# Schematic.net
KiCad netlist of a schematic drawn in EAGLE
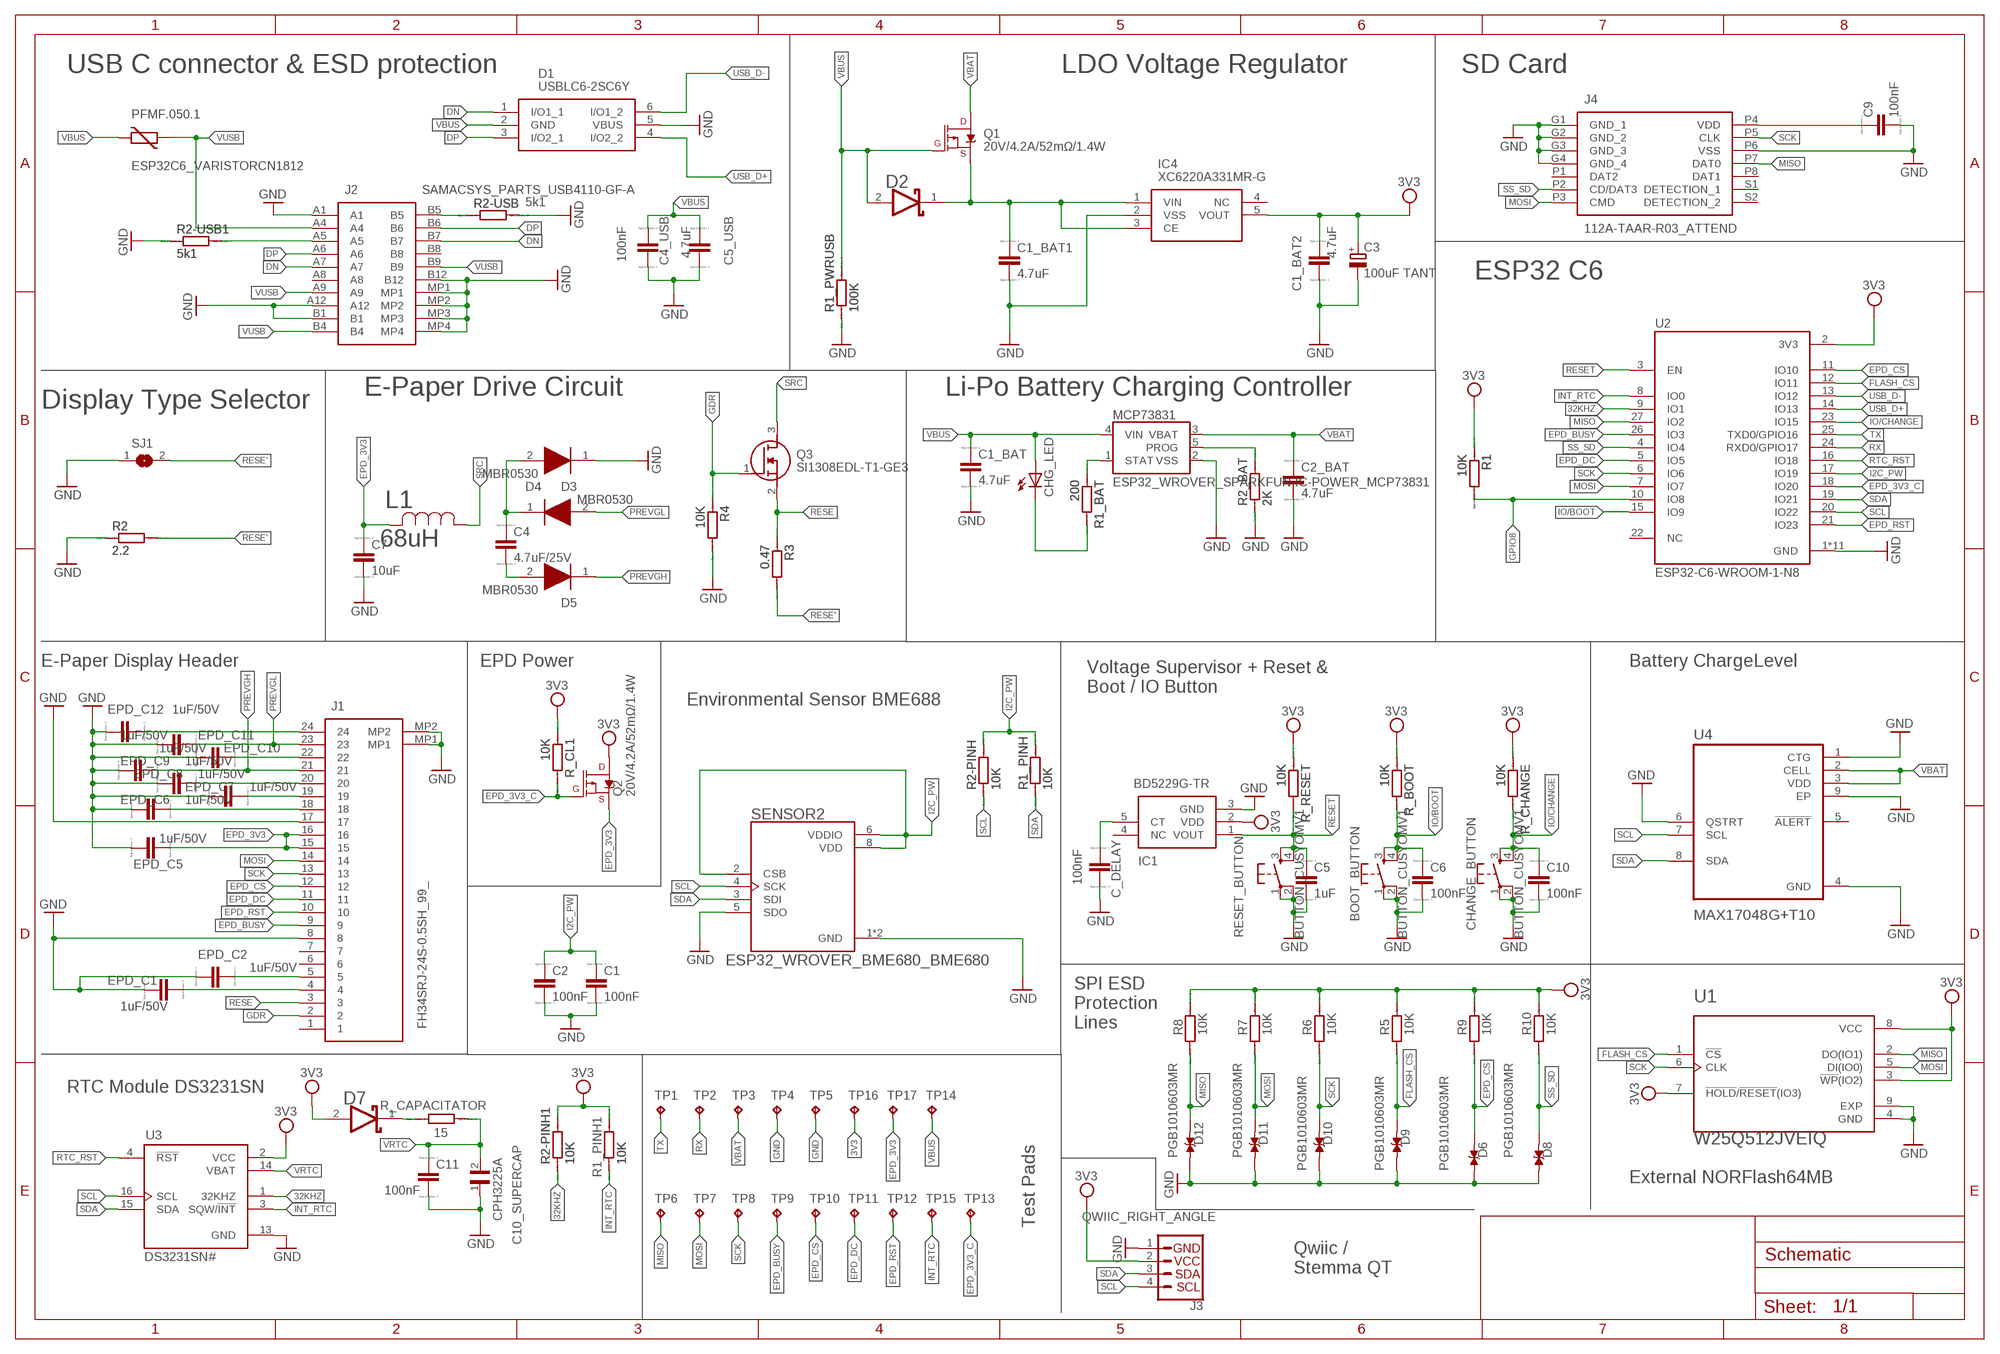
[diagram p0: schematic, sheet 1]

(export (version "E")
  (design (tool "Eeschema 10.0.6"))
  (components
    (comp (ref "BOOT_BUTTON")
      (value "BUTTON_CUSYOMV1")
      (footprint "eagle-import:MYBUTTON")
      (libsource (lib "eagle-import") (part "BUTTON_CUSYOMV1"))
    )
    (comp (ref "C1")
      (value "100nF")
      (footprint "eagle-import:EAGLE-LTSPICE_C0402")
      (libsource (lib "eagle-import") (part "EAGLE-LTSPICE_CC0402"))
    )
    (comp (ref "C1_BAT")
      (value "4.7uF")
      (footprint "eagle-import:EAGLE-LTSPICE_C0402")
      (libsource (lib "eagle-import") (part "EAGLE-LTSPICE_CC0402"))
    )
    (comp (ref "C1_BAT1")
      (value "4.7uF")
      (footprint "eagle-import:EAGLE-LTSPICE_C0402")
      (libsource (lib "eagle-import") (part "EAGLE-LTSPICE_CC0402"))
    )
    (comp (ref "C1_BAT2")
      (value "4.7uF")
      (footprint "eagle-import:ESP32_WROVER_EAGLE-LTSPICE_C0402")
      (libsource (lib "eagle-import") (part "ESP32_WROVER_EAGLE-LTSPICE_CC0402"))
    )
    (comp (ref "C2")
      (value "100nF")
      (footprint "eagle-import:EAGLE-LTSPICE_C0402")
      (libsource (lib "eagle-import") (part "EAGLE-LTSPICE_CC0402"))
    )
    (comp (ref "C2_BAT")
      (value "4.7uF")
      (footprint "eagle-import:ESP32_WROVER_EAGLE-LTSPICE_C0402")
      (libsource (lib "eagle-import") (part "ESP32_WROVER_EAGLE-LTSPICE_CC0402"))
    )
    (comp (ref "C3")
      (value "100uF TANT")
      (footprint "eagle-import:RCL_CT3528")
      (libsource (lib "eagle-import") (part "RCL_CPOL-EUCT3528"))
    )
    (comp (ref "C4")
      (value "4.7uF/25V")
      (footprint "eagle-import:ESP32_WROVER_EAGLE-LTSPICE_C0402")
      (libsource (lib "eagle-import") (part "ESP32_WROVER_EAGLE-LTSPICE_CC0402"))
    )
    (comp (ref "C4_USB")
      (value "100nF")
      (footprint "eagle-import:EAGLE-LTSPICE_C0402")
      (libsource (lib "eagle-import") (part "EAGLE-LTSPICE_CC0402"))
    )
    (comp (ref "C5")
      (value "1uF")
      (footprint "eagle-import:EAGLE-LTSPICE_C0402")
      (libsource (lib "eagle-import") (part "EAGLE-LTSPICE_CC0402"))
    )
    (comp (ref "C5_USB")
      (value "4.7uF")
      (footprint "eagle-import:EAGLE-LTSPICE_C0402")
      (libsource (lib "eagle-import") (part "EAGLE-LTSPICE_CC0402"))
    )
    (comp (ref "C6")
      (value "100nF")
      (footprint "eagle-import:EAGLE-LTSPICE_C0402")
      (libsource (lib "eagle-import") (part "EAGLE-LTSPICE_CC0402"))
    )
    (comp (ref "C7")
      (value "10uF")
      (footprint "eagle-import:EAGLE-LTSPICE_C0402")
      (libsource (lib "eagle-import") (part "EAGLE-LTSPICE_CC0402"))
    )
    (comp (ref "C9")
      (value "100nF")
      (footprint "eagle-import:ESP32_WROVER_EAGLE-LTSPICE_C0402")
      (libsource (lib "eagle-import") (part "ESP32_WROVER_EAGLE-LTSPICE_CC0402"))
    )
    (comp (ref "C10")
      (value "100nF")
      (footprint "eagle-import:EAGLE-LTSPICE_C0402")
      (libsource (lib "eagle-import") (part "EAGLE-LTSPICE_CC0402"))
    )
    (comp (ref "C10_SUPERCAP")
      (value "CPH3225A")
      (footprint "eagle-import:CAPCP3225X100N")
      (fields (field (name "MF") "Seiko Instruments"))
      (libsource (lib "eagle-import") (part "CPH3225A"))
    )
    (comp (ref "C11")
      (value "100nF")
      (footprint "eagle-import:ESP32_WROVER_EAGLE-LTSPICE_C0402")
      (libsource (lib "eagle-import") (part "ESP32_WROVER_EAGLE-LTSPICE_CC0402"))
    )
    (comp (ref "CHANGE_BUTTON")
      (value "BUTTON_CUSYOMV1")
      (footprint "eagle-import:MYBUTTON")
      (libsource (lib "eagle-import") (part "BUTTON_CUSYOMV1"))
    )
    (comp (ref "CHG_LED")
      (value "ADAFRUIT_LEDCHIP-LED0603")
      (footprint "eagle-import:ADAFRUIT_CHIP-LED0603")
      (libsource (lib "eagle-import") (part "ADAFRUIT_LEDCHIP-LED0603"))
    )
    (comp (ref "C_DELAY")
      (value "100nF")
      (footprint "eagle-import:EAGLE-LTSPICE_C0402")
      (libsource (lib "eagle-import") (part "EAGLE-LTSPICE_CC0402"))
    )
    (comp (ref "D1")
      (value "USBLC6-2SC6Y")
      (footprint "eagle-import:SOT95P280X145-6N")
      (fields (field (name "MF") "STMicroelectronics"))
      (libsource (lib "eagle-import") (part "USBLC6-2SC6Y"))
    )
    (comp (ref "D2")
      (value "ESP32_WROVER_AVX---SD0805S020S1R0_AVX_SD0805S020S1R0_0_0AVX_SD0805S020S1R0_0_0")
      (footprint "eagle-import:ESP32_WROVER_AVX---SD0805S020S1R0_AVX_SD0805S020S1R0_0")
      (fields
        (field (name "DIGIKEY_PART_NUMBER") "478-7800-1-ND")
        (field (name "MF") "AVX")
        (field (name "MOUSER_PART_NUMBER") "581-SD0805S020S1R0")
      )
      (libsource (lib "eagle-import") (part "ESP32_WROVER_AVX---SD0805S020S1R0_AVX_SD0805S020S1R0_0_0AVX_SD0805S020S1R0_0_0"))
    )
    (comp (ref "D3")
      (value "MBR0530")
      (footprint "eagle-import:SOD3716X135N")
      (fields (field (name "MF") "ON Semiconductor"))
      (libsource (lib "eagle-import") (part "MBR0530"))
    )
    (comp (ref "D4")
      (value "MBR0530")
      (footprint "eagle-import:SOD3716X135N")
      (fields (field (name "MF") "ON Semiconductor"))
      (libsource (lib "eagle-import") (part "MBR0530"))
    )
    (comp (ref "D5")
      (value "MBR0530")
      (footprint "eagle-import:SOD3716X135N")
      (fields (field (name "MF") "ON Semiconductor"))
      (libsource (lib "eagle-import") (part "MBR0530"))
    )
    (comp (ref "D6")
      (value "PGB1010603MR")
      (footprint "eagle-import:DIOC1608X36N")
      (fields (field (name "MF") "Littelfuse Inc."))
      (libsource (lib "eagle-import") (part "PGB1010603MR"))
    )
    (comp (ref "D7")
      (value "ESP32_WROVER_AVX---SD0805S020S1R0_AVX_SD0805S020S1R0_0_0AVX_SD0805S020S1R0_0_0")
      (footprint "eagle-import:ESP32_WROVER_AVX---SD0805S020S1R0_AVX_SD0805S020S1R0_0")
      (fields
        (field (name "DIGIKEY_PART_NUMBER") "478-7800-1-ND")
        (field (name "MF") "AVX")
        (field (name "MOUSER_PART_NUMBER") "581-SD0805S020S1R0")
      )
      (libsource (lib "eagle-import") (part "ESP32_WROVER_AVX---SD0805S020S1R0_AVX_SD0805S020S1R0_0_0AVX_SD0805S020S1R0_0_0"))
    )
    (comp (ref "D8")
      (value "PGB1010603MR")
      (footprint "eagle-import:DIOC1608X36N")
      (fields (field (name "MF") "Littelfuse Inc."))
      (libsource (lib "eagle-import") (part "PGB1010603MR"))
    )
    (comp (ref "D9")
      (value "PGB1010603MR")
      (footprint "eagle-import:DIOC1608X36N")
      (fields (field (name "MF") "Littelfuse Inc."))
      (libsource (lib "eagle-import") (part "PGB1010603MR"))
    )
    (comp (ref "D10")
      (value "PGB1010603MR")
      (footprint "eagle-import:DIOC1608X36N")
      (fields (field (name "MF") "Littelfuse Inc."))
      (libsource (lib "eagle-import") (part "PGB1010603MR"))
    )
    (comp (ref "D11")
      (value "PGB1010603MR")
      (footprint "eagle-import:DIOC1608X36N")
      (fields (field (name "MF") "Littelfuse Inc."))
      (libsource (lib "eagle-import") (part "PGB1010603MR"))
    )
    (comp (ref "D12")
      (value "PGB1010603MR")
      (footprint "eagle-import:DIOC1608X36N")
      (fields (field (name "MF") "Littelfuse Inc."))
      (libsource (lib "eagle-import") (part "PGB1010603MR"))
    )
    (comp (ref "EPD_C1")
      (value "1uF/50V")
      (footprint "eagle-import:EAGLE-LTSPICE_C0402")
      (libsource (lib "eagle-import") (part "EAGLE-LTSPICE_CC0402"))
    )
    (comp (ref "EPD_C2")
      (value "1uF/50V")
      (footprint "eagle-import:EAGLE-LTSPICE_C0402")
      (libsource (lib "eagle-import") (part "EAGLE-LTSPICE_CC0402"))
    )
    (comp (ref "EPD_C5")
      (value "1uF/50V")
      (footprint "eagle-import:EAGLE-LTSPICE_C0402")
      (libsource (lib "eagle-import") (part "EAGLE-LTSPICE_CC0402"))
    )
    (comp (ref "EPD_C6")
      (value "1uF/50V")
      (footprint "eagle-import:EAGLE-LTSPICE_C0402")
      (libsource (lib "eagle-import") (part "EAGLE-LTSPICE_CC0402"))
    )
    (comp (ref "EPD_C7")
      (value "1uF/50V")
      (footprint "eagle-import:EAGLE-LTSPICE_C0402")
      (libsource (lib "eagle-import") (part "EAGLE-LTSPICE_CC0402"))
    )
    (comp (ref "EPD_C8")
      (value "1uF/50V")
      (footprint "eagle-import:EAGLE-LTSPICE_C0402")
      (libsource (lib "eagle-import") (part "EAGLE-LTSPICE_CC0402"))
    )
    (comp (ref "EPD_C9")
      (value "1uF/50V")
      (footprint "eagle-import:EAGLE-LTSPICE_C0402")
      (libsource (lib "eagle-import") (part "EAGLE-LTSPICE_CC0402"))
    )
    (comp (ref "EPD_C10")
      (value "1uF/50V")
      (footprint "eagle-import:EAGLE-LTSPICE_C0402")
      (libsource (lib "eagle-import") (part "EAGLE-LTSPICE_CC0402"))
    )
    (comp (ref "EPD_C11")
      (value "1uF/50V")
      (footprint "eagle-import:EAGLE-LTSPICE_C0402")
      (libsource (lib "eagle-import") (part "EAGLE-LTSPICE_CC0402"))
    )
    (comp (ref "EPD_C12")
      (value "1uF/50V")
      (footprint "eagle-import:EAGLE-LTSPICE_C0402")
      (libsource (lib "eagle-import") (part "EAGLE-LTSPICE_CC0402"))
    )
    (comp (ref "IC1")
      (value "BD5229G-TR")
      (footprint "eagle-import:SOT95P280X125-5N")
      (fields (field (name "MOUSER_PART_NUMBER") "755-BD5229G-TR"))
      (libsource (lib "eagle-import") (part "BD5229G-TR"))
    )
    (comp (ref "IC4")
      (value "XC6220A331MR-G")
      (footprint "eagle-import:SOT95P280X120-5N")
      (fields (field (name "MOUSER_PART_NUMBER") "865-XC6220A331MR-G"))
      (libsource (lib "eagle-import") (part "XC6220A331MR-G"))
    )
    (comp (ref "J1")
      (value "FH34SRJ-24S-0.5SH_99_")
      (footprint "eagle-import:FH34SRJ24S05SH99")
      (fields
        (field (name "MANUFACTURER_PART_NUMBER") "FH34SRJ-24S-0.5SH(99)")
        (field (name "MOUSER_PART_NUMBER") "798-FH34SRJ24S05SH99")
      )
      (libsource (lib "eagle-import") (part "FH34SRJ-24S-0.5SH_99_"))
    )
    (comp (ref "J2")
      (value "SAMACSYS_PARTS_USB4110-GF-A")
      (footprint "eagle-import:SAMACSYS_PARTS_USB4110GFA")
      (fields
        (field (name "MANUFACTURER_PART_NUMBER") "USB4110-GF-A")
        (field (name "MOUSER_PART_NUMBER") "640-USB4110-GF-A")
      )
      (libsource (lib "eagle-import") (part "SAMACSYS_PARTS_USB4110-GF-A"))
    )
    (comp (ref "J3")
      (value "QWIIC_RIGHT_ANGLE")
      (footprint "eagle-import:JST04_1MM_RA")
      (libsource (lib "eagle-import") (part "QWIIC_CONNECTORJS-1MM"))
    )
    (comp (ref "J4")
      (value "112A-TAAR-R03_ATTEND")
      (footprint "eagle-import:112ATAARR03ATTEND")
      (fields (field (name "MANUFACTURER_PART_NUMBER") "112A-TAAR-R03 ATTEND"))
      (libsource (lib "eagle-import") (part "112A-TAAR-R03_ATTEND"))
    )
    (comp (ref "L1")
      (value "68uH")
      (footprint "eagle-import:IND_4828-WE-TPC_WRE")
      (fields
        (field (name "MANUFACTURER_PART_NUMBER") "744043680")
        (field (name "COPYRIGHT") "Copyright (C) 2024 Ultra Librarian. All rights reserved.")
      )
      (libsource (lib "eagle-import") (part "744043680IND_4828-WE-TPC_WRE"))
    )
    (comp (ref "MCP73831")
      (value "ESP32_WROVER_SPARKFUN-IC-POWER_MCP73831")
      (footprint "eagle-import:ESP32_WROVER_SPARKFUN-IC-POWER_SOT23-5")
      (libsource (lib "eagle-import") (part "ESP32_WROVER_SPARKFUN-IC-POWER_MCP73831"))
    )
    (comp (ref "PFMF.050.1")
      (value "ESP32C6_VARISTORCN1812")
      (footprint "eagle-import:ESP32C6_VARISTOR_CT_CN1812")
      (libsource (lib "eagle-import") (part "ESP32C6_VARISTORCN1812"))
    )
    (comp (ref "Q1")
      (value "20V/4.2A/52mΩ/1.4W")
      (footprint "eagle-import:ESP32_WROVER_SPARKFUN-DISCRETESEMI_SOT23-3")
      (libsource (lib "eagle-import") (part "ESP32_WROVER_SPARKFUN-DISCRETESEMI_MOSFET_PCH-DMG2305UX-7"))
    )
    (comp (ref "Q2")
      (value "20V/4.2A/52mΩ/1.4W")
      (footprint "eagle-import:ESP32_WROVER_SPARKFUN-DISCRETESEMI_SOT23-3")
      (libsource (lib "eagle-import") (part "ESP32_WROVER_SPARKFUN-DISCRETESEMI_MOSFET_PCH-DMG2305UX-7"))
    )
    (comp (ref "Q3")
      (value "SI1308EDL-T1-GE3")
      (footprint "eagle-import:SOT65P210X110-3N")
      (fields (field (name "MF") "Vishay Siliconix"))
      (libsource (lib "eagle-import") (part "SI1308EDL-T1-GE3"))
    )
    (comp (ref "R1")
      (value "10K")
      (footprint "eagle-import:ESP32_WROVER_EAGLE-LTSPICE_R0402")
      (libsource (lib "eagle-import") (part "ESP32_WROVER_EAGLE-LTSPICE_RR0402"))
    )
    (comp (ref "R1_BAT")
      (value "200")
      (footprint "eagle-import:ESP32_WROVER_EAGLE-LTSPICE_R0402")
      (libsource (lib "eagle-import") (part "ESP32_WROVER_EAGLE-LTSPICE_RR0402"))
    )
    (comp (ref "R1_PINH")
      (value "10K")
      (footprint "eagle-import:ESP32_WROVER_EAGLE-LTSPICE_R0402")
      (libsource (lib "eagle-import") (part "ESP32_WROVER_EAGLE-LTSPICE_RR0402"))
    )
    (comp (ref "R1_PINH1")
      (value "10K")
      (footprint "eagle-import:ESP32_WROVER_EAGLE-LTSPICE_R0402")
      (libsource (lib "eagle-import") (part "ESP32_WROVER_EAGLE-LTSPICE_RR0402"))
    )
    (comp (ref "R1_PWRUSB")
      (value "100K")
      (footprint "eagle-import:ESP32_WROVER_EAGLE-LTSPICE_R0402")
      (libsource (lib "eagle-import") (part "ESP32_WROVER_EAGLE-LTSPICE_RR0402"))
    )
    (comp (ref "R2")
      (value "2.2")
      (footprint "eagle-import:ESP32_WROVER_EAGLE-LTSPICE_R0402")
      (libsource (lib "eagle-import") (part "ESP32_WROVER_EAGLE-LTSPICE_RR0402"))
    )
    (comp (ref "R2-PINH")
      (value "10K")
      (footprint "eagle-import:ESP32_WROVER_EAGLE-LTSPICE_R0402")
      (libsource (lib "eagle-import") (part "ESP32_WROVER_EAGLE-LTSPICE_RR0402"))
    )
    (comp (ref "R2-PINH1")
      (value "10K")
      (footprint "eagle-import:ESP32_WROVER_EAGLE-LTSPICE_R0402")
      (libsource (lib "eagle-import") (part "ESP32_WROVER_EAGLE-LTSPICE_RR0402"))
    )
    (comp (ref "R2-USB")
      (value "5k1")
      (footprint "eagle-import:ESP32_WROVER_EAGLE-LTSPICE_R0402")
      (libsource (lib "eagle-import") (part "ESP32_WROVER_EAGLE-LTSPICE_RR0402"))
    )
    (comp (ref "R2-USB1")
      (value "5k1")
      (footprint "eagle-import:ESP32_WROVER_EAGLE-LTSPICE_R0402")
      (libsource (lib "eagle-import") (part "ESP32_WROVER_EAGLE-LTSPICE_RR0402"))
    )
    (comp (ref "R2_BAT")
      (value "2K")
      (footprint "eagle-import:ESP32_WROVER_EAGLE-LTSPICE_R0402")
      (libsource (lib "eagle-import") (part "ESP32_WROVER_EAGLE-LTSPICE_RR0402"))
    )
    (comp (ref "R3")
      (value "0.47")
      (footprint "eagle-import:ESP32_WROVER_EAGLE-LTSPICE_R0402")
      (libsource (lib "eagle-import") (part "ESP32_WROVER_EAGLE-LTSPICE_RR0402"))
    )
    (comp (ref "R4")
      (value "10K")
      (footprint "eagle-import:ESP32_WROVER_EAGLE-LTSPICE_R0402")
      (libsource (lib "eagle-import") (part "ESP32_WROVER_EAGLE-LTSPICE_RR0402"))
    )
    (comp (ref "R5")
      (value "10K")
      (footprint "eagle-import:ESP32_WROVER_EAGLE-LTSPICE_R0402")
      (libsource (lib "eagle-import") (part "ESP32_WROVER_EAGLE-LTSPICE_RR0402"))
    )
    (comp (ref "R6")
      (value "10K")
      (footprint "eagle-import:ESP32_WROVER_EAGLE-LTSPICE_R0402")
      (libsource (lib "eagle-import") (part "ESP32_WROVER_EAGLE-LTSPICE_RR0402"))
    )
    (comp (ref "R7")
      (value "10K")
      (footprint "eagle-import:ESP32_WROVER_EAGLE-LTSPICE_R0402")
      (libsource (lib "eagle-import") (part "ESP32_WROVER_EAGLE-LTSPICE_RR0402"))
    )
    (comp (ref "R8")
      (value "10K")
      (footprint "eagle-import:ESP32_WROVER_EAGLE-LTSPICE_R0402")
      (libsource (lib "eagle-import") (part "ESP32_WROVER_EAGLE-LTSPICE_RR0402"))
    )
    (comp (ref "R9")
      (value "10K")
      (footprint "eagle-import:ESP32_WROVER_EAGLE-LTSPICE_R0402")
      (libsource (lib "eagle-import") (part "ESP32_WROVER_EAGLE-LTSPICE_RR0402"))
    )
    (comp (ref "R10")
      (value "10K")
      (footprint "eagle-import:ESP32_WROVER_EAGLE-LTSPICE_R0402")
      (libsource (lib "eagle-import") (part "ESP32_WROVER_EAGLE-LTSPICE_RR0402"))
    )
    (comp (ref "RESET_BUTTON")
      (value "BUTTON_CUSYOMV1")
      (footprint "eagle-import:MYBUTTON")
      (libsource (lib "eagle-import") (part "BUTTON_CUSYOMV1"))
    )
    (comp (ref "R_BOOT")
      (value "10K")
      (footprint "eagle-import:ESP32_WROVER_EAGLE-LTSPICE_R0402")
      (libsource (lib "eagle-import") (part "ESP32_WROVER_EAGLE-LTSPICE_RR0402"))
    )
    (comp (ref "R_CAPACITATOR")
      (value "15")
      (footprint "eagle-import:ESP32_WROVER_EAGLE-LTSPICE_R0402")
      (libsource (lib "eagle-import") (part "ESP32_WROVER_EAGLE-LTSPICE_RR0402"))
    )
    (comp (ref "R_CHANGE")
      (value "10K")
      (footprint "eagle-import:ESP32_WROVER_EAGLE-LTSPICE_R0402")
      (libsource (lib "eagle-import") (part "ESP32_WROVER_EAGLE-LTSPICE_RR0402"))
    )
    (comp (ref "R_CL1")
      (value "10K")
      (footprint "eagle-import:ESP32_WROVER_EAGLE-LTSPICE_R0402")
      (libsource (lib "eagle-import") (part "ESP32_WROVER_EAGLE-LTSPICE_RR0402"))
    )
    (comp (ref "R_RESET")
      (value "10K")
      (footprint "eagle-import:ESP32_WROVER_EAGLE-LTSPICE_R0402")
      (libsource (lib "eagle-import") (part "ESP32_WROVER_EAGLE-LTSPICE_RR0402"))
    )
    (comp (ref "SENSOR2")
      (value "ESP32_WROVER_BME680_BME680")
      (footprint "eagle-import:ESP32_WROVER_BME680_PSON80P300X300X100-8N")
      (fields (field (name "MF") "Bosch Sensortec") (field (name "MP") "BME680"))
      (libsource (lib "eagle-import") (part "ESP32_WROVER_BME680_BME680"))
    )
    (comp (ref "SJ1") (value "SJ") (footprint "eagle-import:SJ") (libsource (lib "eagle-import") (part "SJ")))
    (comp (ref "TP1")
      (value "TPTP20R")
      (footprint "eagle-import:TP20R")
      (libsource (lib "eagle-import") (part "TPTP20R"))
    )
    (comp (ref "TP2")
      (value "TPTP20R")
      (footprint "eagle-import:TP20R")
      (libsource (lib "eagle-import") (part "TPTP20R"))
    )
    (comp (ref "TP3")
      (value "TPTP20R")
      (footprint "eagle-import:TP20R")
      (libsource (lib "eagle-import") (part "TPTP20R"))
    )
    (comp (ref "TP4")
      (value "TPTP20R")
      (footprint "eagle-import:TP20R")
      (libsource (lib "eagle-import") (part "TPTP20R"))
    )
    (comp (ref "TP5")
      (value "TPTP20R")
      (footprint "eagle-import:TP20R")
      (libsource (lib "eagle-import") (part "TPTP20R"))
    )
    (comp (ref "TP6")
      (value "TPTP20R")
      (footprint "eagle-import:TP20R")
      (libsource (lib "eagle-import") (part "TPTP20R"))
    )
    (comp (ref "TP7")
      (value "TPTP20R")
      (footprint "eagle-import:TP20R")
      (libsource (lib "eagle-import") (part "TPTP20R"))
    )
    (comp (ref "TP8")
      (value "TPTP20R")
      (footprint "eagle-import:TP20R")
      (libsource (lib "eagle-import") (part "TPTP20R"))
    )
    (comp (ref "TP9")
      (value "TPTP20R")
      (footprint "eagle-import:TP20R")
      (libsource (lib "eagle-import") (part "TPTP20R"))
    )
    (comp (ref "TP10")
      (value "TPTP20R")
      (footprint "eagle-import:TP20R")
      (libsource (lib "eagle-import") (part "TPTP20R"))
    )
    (comp (ref "TP11")
      (value "TPTP20R")
      (footprint "eagle-import:TP20R")
      (libsource (lib "eagle-import") (part "TPTP20R"))
    )
    (comp (ref "TP12")
      (value "TPTP20R")
      (footprint "eagle-import:TP20R")
      (libsource (lib "eagle-import") (part "TPTP20R"))
    )
    (comp (ref "TP13")
      (value "TPTP20R")
      (footprint "eagle-import:TP20R")
      (libsource (lib "eagle-import") (part "TPTP20R"))
    )
    (comp (ref "TP14")
      (value "TPTP20R")
      (footprint "eagle-import:TP20R")
      (libsource (lib "eagle-import") (part "TPTP20R"))
    )
    (comp (ref "TP15")
      (value "TPTP20R")
      (footprint "eagle-import:TP20R")
      (libsource (lib "eagle-import") (part "TPTP20R"))
    )
    (comp (ref "TP16")
      (value "TPTP20R")
      (footprint "eagle-import:TP20R")
      (libsource (lib "eagle-import") (part "TPTP20R"))
    )
    (comp (ref "TP17")
      (value "TPTP20R")
      (footprint "eagle-import:TP20R")
      (libsource (lib "eagle-import") (part "TPTP20R"))
    )
    (comp (ref "U1")
      (value "W25Q512JVEIQ")
      (footprint "eagle-import:SON127P600X800X80-9N")
      (fields (field (name "MF") "Winbond Electronics"))
      (libsource (lib "eagle-import") (part "W25Q512JVEIQ"))
    )
    (comp (ref "U2")
      (value "ESP32-C6-WROOM-1-N8")
      (footprint "eagle-import:XCVR_ESP32-C6-WROOM-1-N8")
      (fields (field (name "MF") "Espressif Systems"))
      (libsource (lib "eagle-import") (part "ESP32-C6-WROOM-1-N8"))
    )
    (comp (ref "U3")
      (value "DS3231SN#")
      (footprint "eagle-import:SOIC127P1032X265-16N")
      (fields (field (name "MF") "Analog Devices"))
      (libsource (lib "eagle-import") (part "DS3231SN#"))
    )
    (comp (ref "U4")
      (value "MAX17048G+T10")
      (footprint "eagle-import:SON50P200X200X80-9N")
      (fields (field (name "MF") "Analog Devices"))
      (libsource (lib "eagle-import") (part "MAX17048G+T10"))
    )
  )
  (nets
    (net (code "1") (name "3V3") (class "Default")
      (node (ref "C1_BAT2") (pin "1") (pinfunction "1_1") (pintype "passive"))
      (node (ref "C3") (pin "+") (pinfunction "+_+") (pintype "passive"))
      (node (ref "D7") (pin "2") (pinfunction "ANODE_2") (pintype "bidirectional"))
      (node (ref "IC1") (pin "2") (pinfunction "VDD_2") (pintype "bidirectional"))
      (node (ref "IC4") (pin "5") (pinfunction "VOUT_5") (pintype "bidirectional"))
      (node (ref "J3") (pin "2") (pinfunction "2_2") (pintype "power_in"))
      (node (ref "Q2") (pin "3") (pinfunction "D_3") (pintype "bidirectional"))
      (node (ref "R1") (pin "1") (pinfunction "1_1") (pintype "passive"))
      (node (ref "R10") (pin "2") (pinfunction "2_2") (pintype "passive"))
      (node (ref "R1_PINH1") (pin "2") (pinfunction "2_2") (pintype "passive"))
      (node (ref "R2-PINH1") (pin "2") (pinfunction "2_2") (pintype "passive"))
      (node (ref "R5") (pin "2") (pinfunction "2_2") (pintype "passive"))
      (node (ref "R6") (pin "2") (pinfunction "2_2") (pintype "passive"))
      (node (ref "R7") (pin "2") (pinfunction "2_2") (pintype "passive"))
      (node (ref "R8") (pin "2") (pinfunction "2_2") (pintype "passive"))
      (node (ref "R9") (pin "2") (pinfunction "2_2") (pintype "passive"))
      (node (ref "R_BOOT") (pin "1") (pinfunction "1_1") (pintype "passive"))
      (node (ref "R_CHANGE") (pin "1") (pinfunction "1_1") (pintype "passive"))
      (node (ref "R_CL1") (pin "1") (pinfunction "1_1") (pintype "passive"))
      (node (ref "R_RESET") (pin "1") (pinfunction "1_1") (pintype "passive"))
      (node (ref "TP16") (pin "TP") (pinfunction "TP_TP") (pintype "input"))
      (node (ref "U1") (pin "3") (pinfunction "~{WP}(IO2)_3") (pintype "bidirectional"))
      (node (ref "U1") (pin "7") (pinfunction "~{HOLD}/~{RESET}(IO3)_7") (pintype "bidirectional"))
      (node (ref "U1") (pin "8") (pinfunction "VCC_8") (pintype "power_in"))
      (node (ref "U2") (pin "2") (pinfunction "3V3_2") (pintype "power_in"))
      (node (ref "U3") (pin "2") (pinfunction "VCC_2") (pintype "power_in"))
    )
    (net (code "2") (name "32KHZ") (class "Default")
      (node (ref "R2-PINH1") (pin "1") (pinfunction "1_1") (pintype "passive"))
      (node (ref "U2") (pin "9") (pinfunction "IO1_9") (pintype "bidirectional"))
      (node (ref "U3") (pin "1") (pinfunction "32KHZ_1") (pintype "output"))
    )
    (net (code "3") (name "DN") (class "Default")
      (node (ref "D1") (pin "1") (pinfunction "I/O1_1_1") (pintype "bidirectional"))
      (node (ref "J2") (pin "A7") (pinfunction "A7_A7") (pintype "bidirectional"))
      (node (ref "J2") (pin "B7") (pinfunction "B7_B7") (pintype "bidirectional"))
    )
    (net (code "4") (name "DP") (class "Default")
      (node (ref "D1") (pin "3") (pinfunction "I/O2_1_3") (pintype "bidirectional"))
      (node (ref "J2") (pin "A6") (pinfunction "A6_A6") (pintype "bidirectional"))
      (node (ref "J2") (pin "B6") (pinfunction "B6_B6") (pintype "bidirectional"))
    )
    (net (code "5") (name "EPD_3V3") (class "Default")
      (node (ref "C7") (pin "1") (pinfunction "1_1") (pintype "passive"))
      (node (ref "EPD_C5") (pin "1") (pinfunction "1_1") (pintype "passive"))
      (node (ref "J1") (pin "15") (pinfunction "15_15") (pintype "bidirectional"))
      (node (ref "J1") (pin "16") (pinfunction "16_16") (pintype "bidirectional"))
      (node (ref "L1") (pin "2") (pinfunction "2_2") (pintype "passive"))
      (node (ref "Q2") (pin "2") (pinfunction "S_2") (pintype "bidirectional"))
      (node (ref "TP17") (pin "TP") (pinfunction "TP_TP") (pintype "input"))
    )
    (net (code "6") (name "EPD_3V3_C") (class "Default")
      (node (ref "Q2") (pin "1") (pinfunction "G_1") (pintype "bidirectional"))
      (node (ref "R_CL1") (pin "2") (pinfunction "2_2") (pintype "passive"))
      (node (ref "TP13") (pin "TP") (pinfunction "TP_TP") (pintype "input"))
      (node (ref "U2") (pin "18") (pinfunction "IO20_18") (pintype "bidirectional"))
    )
    (net (code "7") (name "EPD_BUSY") (class "Default")
      (node (ref "J1") (pin "9") (pinfunction "9_9") (pintype "bidirectional"))
      (node (ref "TP9") (pin "TP") (pinfunction "TP_TP") (pintype "input"))
      (node (ref "U2") (pin "26") (pinfunction "IO3_26") (pintype "bidirectional"))
    )
    (net (code "8") (name "EPD_CS") (class "Default")
      (node (ref "D6") (pin "2") (pinfunction "2_2") (pintype "passive"))
      (node (ref "J1") (pin "12") (pinfunction "12_12") (pintype "bidirectional"))
      (node (ref "R9") (pin "1") (pinfunction "1_1") (pintype "passive"))
      (node (ref "TP10") (pin "TP") (pinfunction "TP_TP") (pintype "input"))
      (node (ref "U2") (pin "11") (pinfunction "IO10_11") (pintype "bidirectional"))
    )
    (net (code "9") (name "EPD_DC") (class "Default")
      (node (ref "J1") (pin "11") (pinfunction "11_11") (pintype "bidirectional"))
      (node (ref "TP11") (pin "TP") (pinfunction "TP_TP") (pintype "input"))
      (node (ref "U2") (pin "5") (pinfunction "IO5_5") (pintype "bidirectional"))
    )
    (net (code "10") (name "EPD_RST") (class "Default")
      (node (ref "J1") (pin "10") (pinfunction "10_10") (pintype "bidirectional"))
      (node (ref "TP12") (pin "TP") (pinfunction "TP_TP") (pintype "input"))
      (node (ref "U2") (pin "21") (pinfunction "IO23_21") (pintype "bidirectional"))
    )
    (net (code "11") (name "FLASH_CS") (class "Default")
      (node (ref "D9") (pin "2") (pinfunction "2_2") (pintype "passive"))
      (node (ref "R5") (pin "1") (pinfunction "1_1") (pintype "passive"))
      (node (ref "U1") (pin "1") (pinfunction "~{CS}_1") (pintype "input"))
      (node (ref "U2") (pin "12") (pinfunction "IO11_12") (pintype "bidirectional"))
    )
    (net (code "12") (name "GDR") (class "Default")
      (node (ref "J1") (pin "2") (pinfunction "2_2") (pintype "bidirectional"))
      (node (ref "Q3") (pin "1") (pinfunction "G_1") (pintype "bidirectional"))
      (node (ref "R4") (pin "1") (pinfunction "1_1") (pintype "passive"))
    )
    (net (code "13") (name "GND") (class "Default")
      (node (ref "BOOT_BUTTON") (pin "1") (pinfunction "1_1") (pintype "passive"))
      (node (ref "BOOT_BUTTON") (pin "2") (pinfunction "2_2") (pintype "passive"))
      (node (ref "C1") (pin "2") (pinfunction "2_2") (pintype "passive"))
      (node (ref "C10") (pin "2") (pinfunction "2_2") (pintype "passive"))
      (node (ref "C10_SUPERCAP") (pin "1") (pinfunction "1_1") (pintype "passive"))
      (node (ref "C11") (pin "2") (pinfunction "2_2") (pintype "passive"))
      (node (ref "C1_BAT") (pin "2") (pinfunction "2_2") (pintype "passive"))
      (node (ref "C1_BAT1") (pin "2") (pinfunction "2_2") (pintype "passive"))
      (node (ref "C1_BAT2") (pin "2") (pinfunction "2_2") (pintype "passive"))
      (node (ref "C2") (pin "2") (pinfunction "2_2") (pintype "passive"))
      (node (ref "C2_BAT") (pin "2") (pinfunction "2_2") (pintype "passive"))
      (node (ref "C3") (pin "-") (pinfunction "-_-") (pintype "passive"))
      (node (ref "C4_USB") (pin "2") (pinfunction "2_2") (pintype "passive"))
      (node (ref "C5") (pin "2") (pinfunction "2_2") (pintype "passive"))
      (node (ref "C5_USB") (pin "2") (pinfunction "2_2") (pintype "passive"))
      (node (ref "C6") (pin "2") (pinfunction "2_2") (pintype "passive"))
      (node (ref "C7") (pin "2") (pinfunction "2_2") (pintype "passive"))
      (node (ref "C9") (pin "2") (pinfunction "2_2") (pintype "passive"))
      (node (ref "CHANGE_BUTTON") (pin "1") (pinfunction "1_1") (pintype "passive"))
      (node (ref "CHANGE_BUTTON") (pin "2") (pinfunction "2_2") (pintype "passive"))
      (node (ref "C_DELAY") (pin "2") (pinfunction "2_2") (pintype "passive"))
      (node (ref "D1") (pin "5") (pinfunction "VBUS_5") (pintype "bidirectional"))
      (node (ref "D10") (pin "1") (pinfunction "1_1") (pintype "passive"))
      (node (ref "D11") (pin "1") (pinfunction "1_1") (pintype "passive"))
      (node (ref "D12") (pin "1") (pinfunction "1_1") (pintype "passive"))
      (node (ref "D3") (pin "1") (pinfunction "K_1") (pintype "bidirectional"))
      (node (ref "D6") (pin "1") (pinfunction "1_1") (pintype "passive"))
      (node (ref "D8") (pin "1") (pinfunction "1_1") (pintype "passive"))
      (node (ref "D9") (pin "1") (pinfunction "1_1") (pintype "passive"))
      (node (ref "EPD_C1") (pin "2") (pinfunction "2_2") (pintype "passive"))
      (node (ref "EPD_C10") (pin "2") (pinfunction "2_2") (pintype "passive"))
      (node (ref "EPD_C11") (pin "2") (pinfunction "2_2") (pintype "passive"))
      (node (ref "EPD_C12") (pin "2") (pinfunction "2_2") (pintype "passive"))
      (node (ref "EPD_C2") (pin "2") (pinfunction "2_2") (pintype "passive"))
      (node (ref "EPD_C5") (pin "2") (pinfunction "2_2") (pintype "passive"))
      (node (ref "EPD_C6") (pin "2") (pinfunction "2_2") (pintype "passive"))
      (node (ref "EPD_C7") (pin "2") (pinfunction "2_2") (pintype "passive"))
      (node (ref "EPD_C8") (pin "2") (pinfunction "2_2") (pintype "passive"))
      (node (ref "EPD_C9") (pin "2") (pinfunction "2_2") (pintype "passive"))
      (node (ref "IC1") (pin "3") (pinfunction "GND_3") (pintype "bidirectional"))
      (node (ref "IC4") (pin "2") (pinfunction "VSS_2") (pintype "bidirectional"))
      (node (ref "J1") (pin "17") (pinfunction "17_17") (pintype "bidirectional"))
      (node (ref "J1") (pin "8") (pinfunction "8_8") (pintype "bidirectional"))
      (node (ref "J1") (pin "MP1") (pinfunction "MP1_MP1") (pintype "bidirectional"))
      (node (ref "J1") (pin "MP2") (pinfunction "MP2_MP2") (pintype "bidirectional"))
      (node (ref "J2") (pin "A1") (pinfunction "A1_A1") (pintype "bidirectional"))
      (node (ref "J2") (pin "A12") (pinfunction "A12_A12") (pintype "bidirectional"))
      (node (ref "J2") (pin "B1") (pinfunction "B1_B1") (pintype "bidirectional"))
      (node (ref "J2") (pin "B12") (pinfunction "B12_B12") (pintype "bidirectional"))
      (node (ref "J2") (pin "MP1") (pinfunction "MP1_MP1") (pintype "bidirectional"))
      (node (ref "J2") (pin "MP2") (pinfunction "MP2_MP2") (pintype "bidirectional"))
      (node (ref "J2") (pin "MP3") (pinfunction "MP3_MP3") (pintype "bidirectional"))
      (node (ref "J2") (pin "MP4") (pinfunction "MP4_MP4") (pintype "bidirectional"))
      (node (ref "J3") (pin "1") (pinfunction "1_1") (pintype "power_in"))
      (node (ref "J4") (pin "G1") (pinfunction "GND_1_G1") (pintype "bidirectional"))
      (node (ref "J4") (pin "G2") (pinfunction "GND_2_G2") (pintype "bidirectional"))
      (node (ref "J4") (pin "G3") (pinfunction "GND_3_G3") (pintype "bidirectional"))
      (node (ref "J4") (pin "G4") (pinfunction "GND_4_G4") (pintype "bidirectional"))
      (node (ref "J4") (pin "P6") (pinfunction "VSS_P6") (pintype "bidirectional"))
      (node (ref "MCP73831") (pin "2") (pinfunction "VSS_2") (pintype "power_in"))
      (node (ref "R1_PWRUSB") (pin "1") (pinfunction "1_1") (pintype "passive"))
      (node (ref "R2") (pin "1") (pinfunction "1_1") (pintype "passive"))
      (node (ref "R2-USB") (pin "2") (pinfunction "2_2") (pintype "passive"))
      (node (ref "R2-USB1") (pin "1") (pinfunction "1_1") (pintype "passive"))
      (node (ref "R2_BAT") (pin "1") (pinfunction "1_1") (pintype "passive"))
      (node (ref "R4") (pin "2") (pinfunction "2_2") (pintype "passive"))
      (node (ref "RESET_BUTTON") (pin "1") (pinfunction "1_1") (pintype "passive"))
      (node (ref "RESET_BUTTON") (pin "2") (pinfunction "2_2") (pintype "passive"))
      (node (ref "SENSOR2") (pin "1") (pinfunction "GND_1") (pintype "power_in"))
      (node (ref "SENSOR2") (pin "5") (pinfunction "SDO_5") (pintype "bidirectional"))
      (node (ref "SENSOR2") (pin "7") (pinfunction "GND_7") (pintype "power_in"))
      (node (ref "SJ1") (pin "1") (pinfunction "1_1") (pintype "passive"))
      (node (ref "TP4") (pin "TP") (pinfunction "TP_TP") (pintype "input"))
      (node (ref "TP5") (pin "TP") (pinfunction "TP_TP") (pintype "input"))
      (node (ref "U1") (pin "4") (pinfunction "GND_4") (pintype "power_in"))
      (node (ref "U1") (pin "9") (pinfunction "EXP_9") (pintype "passive"))
      (node (ref "U2") (pin "1") (pinfunction "GND_1") (pintype "power_in"))
      (node (ref "U2") (pin "28") (pinfunction "GND_28") (pintype "power_in"))
      (node (ref "U2") (pin "29_1") (pinfunction "GND_29_1") (pintype "power_in"))
      (node (ref "U2") (pin "29_2") (pinfunction "GND_29_2") (pintype "power_in"))
      (node (ref "U2") (pin "29_3") (pinfunction "GND_29_3") (pintype "power_in"))
      (node (ref "U2") (pin "29_4") (pinfunction "GND_29_4") (pintype "power_in"))
      (node (ref "U2") (pin "29_5") (pinfunction "GND_29_5") (pintype "power_in"))
      (node (ref "U2") (pin "29_6") (pinfunction "GND_29_6") (pintype "power_in"))
      (node (ref "U2") (pin "29_7") (pinfunction "GND_29_7") (pintype "power_in"))
      (node (ref "U2") (pin "29_8") (pinfunction "GND_29_8") (pintype "power_in"))
      (node (ref "U2") (pin "29_9") (pinfunction "GND_29_9") (pintype "power_in"))
      (node (ref "U3") (pin "13") (pinfunction "GND_13") (pintype "power_in"))
      (node (ref "U4") (pin "1") (pinfunction "CTG_1") (pintype "power_in"))
      (node (ref "U4") (pin "4") (pinfunction "GND_4") (pintype "power_in"))
      (node (ref "U4") (pin "6") (pinfunction "QSTRT_6") (pintype "input"))
      (node (ref "U4") (pin "9") (pinfunction "EP_9") (pintype "power_in"))
    )
    (net (code "14") (name "GPIO8") (class "Default")
      (node (ref "R1") (pin "2") (pinfunction "2_2") (pintype "passive"))
      (node (ref "U2") (pin "10") (pinfunction "IO8_10") (pintype "bidirectional"))
    )
    (net (code "15") (name "I2C_PW") (class "Default")
      (node (ref "C1") (pin "1") (pinfunction "1_1") (pintype "passive"))
      (node (ref "C2") (pin "1") (pinfunction "1_1") (pintype "passive"))
      (node (ref "R1_PINH") (pin "2") (pinfunction "2_2") (pintype "passive"))
      (node (ref "R2-PINH") (pin "2") (pinfunction "2_2") (pintype "passive"))
      (node (ref "SENSOR2") (pin "2") (pinfunction "CSB_2") (pintype "input"))
      (node (ref "SENSOR2") (pin "6") (pinfunction "VDDIO_6") (pintype "power_in"))
      (node (ref "SENSOR2") (pin "8") (pinfunction "VDD_8") (pintype "power_in"))
      (node (ref "U2") (pin "17") (pinfunction "IO19_17") (pintype "bidirectional"))
    )
    (net (code "16") (name "INT_RTC") (class "Default")
      (node (ref "R1_PINH1") (pin "1") (pinfunction "1_1") (pintype "passive"))
      (node (ref "TP15") (pin "TP") (pinfunction "TP_TP") (pintype "input"))
      (node (ref "U2") (pin "8") (pinfunction "IO0_8") (pintype "bidirectional"))
      (node (ref "U3") (pin "3") (pinfunction "SQW/~{INT}_3") (pintype "output"))
    )
    (net (code "17") (name "IO{slash}BOOT") (class "Default")
      (node (ref "BOOT_BUTTON") (pin "3") (pinfunction "3_3") (pintype "passive"))
      (node (ref "BOOT_BUTTON") (pin "4") (pinfunction "4_4") (pintype "passive"))
      (node (ref "C6") (pin "1") (pinfunction "1_1") (pintype "passive"))
      (node (ref "R_BOOT") (pin "2") (pinfunction "2_2") (pintype "passive"))
      (node (ref "U2") (pin "15") (pinfunction "IO9_15") (pintype "bidirectional"))
    )
    (net (code "18") (name "IO{slash}CHANGE") (class "Default")
      (node (ref "C10") (pin "1") (pinfunction "1_1") (pintype "passive"))
      (node (ref "CHANGE_BUTTON") (pin "3") (pinfunction "3_3") (pintype "passive"))
      (node (ref "CHANGE_BUTTON") (pin "4") (pinfunction "4_4") (pintype "passive"))
      (node (ref "R_CHANGE") (pin "2") (pinfunction "2_2") (pintype "passive"))
      (node (ref "U2") (pin "23") (pinfunction "IO15_23") (pintype "bidirectional"))
    )
    (net (code "19") (name "MISO") (class "Default")
      (node (ref "D12") (pin "2") (pinfunction "2_2") (pintype "passive"))
      (node (ref "J4") (pin "P7") (pinfunction "DAT0_P7") (pintype "bidirectional"))
      (node (ref "R8") (pin "1") (pinfunction "1_1") (pintype "passive"))
      (node (ref "TP6") (pin "TP") (pinfunction "TP_TP") (pintype "input"))
      (node (ref "U1") (pin "2") (pinfunction "DO(IO1)_2") (pintype "bidirectional"))
      (node (ref "U2") (pin "27") (pinfunction "IO2_27") (pintype "bidirectional"))
    )
    (net (code "20") (name "MOSI") (class "Default")
      (node (ref "D11") (pin "2") (pinfunction "2_2") (pintype "passive"))
      (node (ref "J1") (pin "14") (pinfunction "14_14") (pintype "bidirectional"))
      (node (ref "J4") (pin "P3") (pinfunction "CMD_P3") (pintype "bidirectional"))
      (node (ref "R7") (pin "1") (pinfunction "1_1") (pintype "passive"))
      (node (ref "TP7") (pin "TP") (pinfunction "TP_TP") (pintype "input"))
      (node (ref "U1") (pin "5") (pinfunction "DI(IO0)_5") (pintype "bidirectional"))
      (node (ref "U2") (pin "7") (pinfunction "IO7_7") (pintype "bidirectional"))
    )
    (net (code "21") (name "Net-(CHG_LED-PadC)") (class "Default")
      (node (ref "CHG_LED") (pin "C") (pinfunction "C_C") (pintype "passive"))
      (node (ref "R1_BAT") (pin "2") (pinfunction "2_2") (pintype "passive"))
    )
    (net (code "22") (name "Net-(D2-CATHODE)") (class "Default")
      (node (ref "C1_BAT1") (pin "1") (pinfunction "1_1") (pintype "passive"))
      (node (ref "D2") (pin "1") (pinfunction "CATHODE_1") (pintype "bidirectional"))
      (node (ref "IC4") (pin "1") (pinfunction "VIN_1") (pintype "bidirectional"))
      (node (ref "IC4") (pin "3") (pinfunction "CE_3") (pintype "bidirectional"))
      (node (ref "Q1") (pin "2") (pinfunction "S_2") (pintype "bidirectional"))
    )
    (net (code "23") (name "Net-(D3-A)") (class "Default")
      (node (ref "C4") (pin "1") (pinfunction "1_1") (pintype "passive"))
      (node (ref "D3") (pin "2") (pinfunction "A_2") (pintype "bidirectional"))
      (node (ref "D4") (pin "1") (pinfunction "K_1") (pintype "bidirectional"))
    )
    (net (code "24") (name "Net-(D5-A)") (class "Default")
      (node (ref "C4") (pin "2") (pinfunction "2_2") (pintype "passive"))
      (node (ref "D5") (pin "2") (pinfunction "A_2") (pintype "bidirectional"))
    )
    (net (code "25") (name "Net-(D7-CATHODE)") (class "Default")
      (node (ref "D7") (pin "1") (pinfunction "CATHODE_1") (pintype "bidirectional"))
      (node (ref "R_CAPACITATOR") (pin "2") (pinfunction "2_2") (pintype "passive"))
    )
    (net (code "26") (name "Net-(EPD_C1-Pad1)") (class "Default")
      (node (ref "EPD_C1") (pin "1") (pinfunction "1_1") (pintype "passive"))
      (node (ref "J1") (pin "4") (pinfunction "4_4") (pintype "bidirectional"))
    )
    (net (code "27") (name "Net-(EPD_C2-Pad1)") (class "Default")
      (node (ref "EPD_C2") (pin "1") (pinfunction "1_1") (pintype "passive"))
      (node (ref "J1") (pin "5") (pinfunction "5_5") (pintype "bidirectional"))
    )
    (net (code "28") (name "Net-(EPD_C6-Pad1)") (class "Default")
      (node (ref "EPD_C6") (pin "1") (pinfunction "1_1") (pintype "passive"))
      (node (ref "J1") (pin "18") (pinfunction "18_18") (pintype "bidirectional"))
    )
    (net (code "29") (name "Net-(EPD_C7-Pad1)") (class "Default")
      (node (ref "EPD_C7") (pin "1") (pinfunction "1_1") (pintype "passive"))
      (node (ref "J1") (pin "19") (pinfunction "19_19") (pintype "bidirectional"))
    )
    (net (code "30") (name "Net-(EPD_C8-Pad1)") (class "Default")
      (node (ref "EPD_C8") (pin "1") (pinfunction "1_1") (pintype "passive"))
      (node (ref "J1") (pin "20") (pinfunction "20_20") (pintype "bidirectional"))
    )
    (net (code "31") (name "Net-(EPD_C10-Pad1)") (class "Default")
      (node (ref "EPD_C10") (pin "1") (pinfunction "1_1") (pintype "passive"))
      (node (ref "J1") (pin "22") (pinfunction "22_22") (pintype "bidirectional"))
    )
    (net (code "32") (name "Net-(EPD_C12-Pad1)") (class "Default")
      (node (ref "EPD_C12") (pin "1") (pinfunction "1_1") (pintype "passive"))
      (node (ref "J1") (pin "24") (pinfunction "24_24") (pintype "bidirectional"))
    )
    (net (code "33") (name "Net-(IC1-CT)") (class "Default")
      (node (ref "C_DELAY") (pin "1") (pinfunction "1_1") (pintype "passive"))
      (node (ref "IC1") (pin "5") (pinfunction "CT_5") (pintype "bidirectional"))
    )
    (net (code "34") (name "Net-(J2-PadA5)") (class "Default")
      (node (ref "J2") (pin "A5") (pinfunction "A5_A5") (pintype "bidirectional"))
      (node (ref "R2-USB1") (pin "2") (pinfunction "2_2") (pintype "passive"))
    )
    (net (code "35") (name "Net-(J2-PadB5)") (class "Default")
      (node (ref "J2") (pin "B5") (pinfunction "B5_B5") (pintype "bidirectional"))
      (node (ref "R2-USB") (pin "1") (pinfunction "1_1") (pintype "passive"))
    )
    (net (code "36") (name "Net-(J4-VDD)") (class "Default")
      (node (ref "C9") (pin "1") (pinfunction "1_1") (pintype "passive"))
      (node (ref "J4") (pin "P4") (pinfunction "VDD_P4") (pintype "bidirectional"))
    )
    (net (code "37") (name "Net-(MCP73831-PROG)") (class "Default")
      (node (ref "MCP73831") (pin "5") (pinfunction "PROG_5") (pintype "input"))
      (node (ref "R2_BAT") (pin "2") (pinfunction "2_2") (pintype "passive"))
    )
    (net (code "38") (name "Net-(MCP73831-STAT)") (class "Default")
      (node (ref "MCP73831") (pin "1") (pinfunction "STAT_1") (pintype "output"))
      (node (ref "R1_BAT") (pin "1") (pinfunction "1_1") (pintype "passive"))
    )
    (net (code "39") (name "PREVGH") (class "Default")
      (node (ref "D5") (pin "1") (pinfunction "K_1") (pintype "bidirectional"))
      (node (ref "EPD_C9") (pin "1") (pinfunction "1_1") (pintype "passive"))
      (node (ref "J1") (pin "21") (pinfunction "21_21") (pintype "bidirectional"))
    )
    (net (code "40") (name "PREVGL") (class "Default")
      (node (ref "D4") (pin "2") (pinfunction "A_2") (pintype "bidirectional"))
      (node (ref "EPD_C11") (pin "1") (pinfunction "1_1") (pintype "passive"))
      (node (ref "J1") (pin "23") (pinfunction "23_23") (pintype "bidirectional"))
    )
    (net (code "41") (name "RESE") (class "Default")
      (node (ref "J1") (pin "3") (pinfunction "3_3") (pintype "bidirectional"))
      (node (ref "Q3") (pin "2") (pinfunction "S_2") (pintype "bidirectional"))
      (node (ref "R3") (pin "1") (pinfunction "1_1") (pintype "passive"))
    )
    (net (code "42") (name "RESE'") (class "Default")
      (node (ref "R2") (pin "2") (pinfunction "2_2") (pintype "passive"))
      (node (ref "R3") (pin "2") (pinfunction "2_2") (pintype "passive"))
      (node (ref "SJ1") (pin "2") (pinfunction "2_2") (pintype "passive"))
    )
    (net (code "43") (name "RESET") (class "Default")
      (node (ref "C5") (pin "1") (pinfunction "1_1") (pintype "passive"))
      (node (ref "IC1") (pin "1") (pinfunction "VOUT_1") (pintype "bidirectional"))
      (node (ref "RESET_BUTTON") (pin "3") (pinfunction "3_3") (pintype "passive"))
      (node (ref "RESET_BUTTON") (pin "4") (pinfunction "4_4") (pintype "passive"))
      (node (ref "R_RESET") (pin "2") (pinfunction "2_2") (pintype "passive"))
      (node (ref "U2") (pin "3") (pinfunction "EN_3") (pintype "input"))
    )
    (net (code "44") (name "RTC_RST") (class "Default")
      (node (ref "U2") (pin "16") (pinfunction "IO18_16") (pintype "bidirectional"))
      (node (ref "U3") (pin "4") (pinfunction "~{RST}_4") (pintype "input"))
    )
    (net (code "45") (name "RX") (class "Default")
      (node (ref "TP2") (pin "TP") (pinfunction "TP_TP") (pintype "input"))
      (node (ref "U2") (pin "24") (pinfunction "RXD0/GPIO17_24") (pintype "bidirectional"))
    )
    (net (code "46") (name "SCK") (class "Default")
      (node (ref "D10") (pin "2") (pinfunction "2_2") (pintype "passive"))
      (node (ref "J1") (pin "13") (pinfunction "13_13") (pintype "bidirectional"))
      (node (ref "J4") (pin "P5") (pinfunction "CLK_P5") (pintype "bidirectional"))
      (node (ref "R6") (pin "1") (pinfunction "1_1") (pintype "passive"))
      (node (ref "TP8") (pin "TP") (pinfunction "TP_TP") (pintype "input"))
      (node (ref "U1") (pin "6") (pinfunction "CLK_6") (pintype "input"))
      (node (ref "U2") (pin "6") (pinfunction "IO6_6") (pintype "bidirectional"))
    )
    (net (code "47") (name "SCL") (class "Default")
      (node (ref "J3") (pin "4") (pinfunction "4_4") (pintype "passive"))
      (node (ref "R2-PINH") (pin "1") (pinfunction "1_1") (pintype "passive"))
      (node (ref "SENSOR2") (pin "4") (pinfunction "SCK_4") (pintype "input"))
      (node (ref "U2") (pin "20") (pinfunction "IO22_20") (pintype "bidirectional"))
      (node (ref "U3") (pin "16") (pinfunction "SCL_16") (pintype "input"))
      (node (ref "U4") (pin "7") (pinfunction "SCL_7") (pintype "input"))
    )
    (net (code "48") (name "SDA") (class "Default")
      (node (ref "J3") (pin "3") (pinfunction "3_3") (pintype "passive"))
      (node (ref "R1_PINH") (pin "1") (pinfunction "1_1") (pintype "passive"))
      (node (ref "SENSOR2") (pin "3") (pinfunction "SDI_3") (pintype "bidirectional"))
      (node (ref "U2") (pin "19") (pinfunction "IO21_19") (pintype "bidirectional"))
      (node (ref "U3") (pin "15") (pinfunction "SDA_15") (pintype "bidirectional"))
      (node (ref "U4") (pin "8") (pinfunction "SDA_8") (pintype "bidirectional"))
    )
    (net (code "49") (name "SRC") (class "Default")
      (node (ref "L1") (pin "1") (pinfunction "1_1") (pintype "passive"))
      (node (ref "Q3") (pin "3") (pinfunction "D_3") (pintype "bidirectional"))
    )
    (net (code "50") (name "SS_SD") (class "Default")
      (node (ref "D8") (pin "2") (pinfunction "2_2") (pintype "passive"))
      (node (ref "J4") (pin "P2") (pinfunction "CD/DAT3_P2") (pintype "bidirectional"))
      (node (ref "R10") (pin "1") (pinfunction "1_1") (pintype "passive"))
      (node (ref "U2") (pin "4") (pinfunction "IO4_4") (pintype "bidirectional"))
    )
    (net (code "51") (name "TX") (class "Default")
      (node (ref "TP1") (pin "TP") (pinfunction "TP_TP") (pintype "input"))
      (node (ref "U2") (pin "25") (pinfunction "TXD0/GPIO16_25") (pintype "bidirectional"))
    )
    (net (code "52") (name "USB_D+") (class "Default")
      (node (ref "D1") (pin "4") (pinfunction "I/O2_2_4") (pintype "bidirectional"))
      (node (ref "U2") (pin "14") (pinfunction "IO13_14") (pintype "bidirectional"))
    )
    (net (code "53") (name "USB_D-") (class "Default")
      (node (ref "D1") (pin "6") (pinfunction "I/O1_2_6") (pintype "bidirectional"))
      (node (ref "U2") (pin "13") (pinfunction "IO12_13") (pintype "bidirectional"))
    )
    (net (code "54") (name "VBAT") (class "Default")
      (node (ref "C2_BAT") (pin "1") (pinfunction "1_1") (pintype "passive"))
      (node (ref "MCP73831") (pin "3") (pinfunction "VBAT_3") (pintype "power_in"))
      (node (ref "Q1") (pin "3") (pinfunction "D_3") (pintype "bidirectional"))
      (node (ref "TP3") (pin "TP") (pinfunction "TP_TP") (pintype "input"))
      (node (ref "U4") (pin "2") (pinfunction "CELL_2") (pintype "power_in"))
      (node (ref "U4") (pin "3") (pinfunction "VDD_3") (pintype "power_in"))
    )
    (net (code "55") (name "VBUS") (class "Default")
      (node (ref "C1_BAT") (pin "1") (pinfunction "1_1") (pintype "passive"))
      (node (ref "C4_USB") (pin "1") (pinfunction "1_1") (pintype "passive"))
      (node (ref "C5_USB") (pin "1") (pinfunction "1_1") (pintype "passive"))
      (node (ref "CHG_LED") (pin "A") (pinfunction "A_A") (pintype "passive"))
      (node (ref "D1") (pin "2") (pinfunction "GND_2") (pintype "bidirectional"))
      (node (ref "D2") (pin "2") (pinfunction "ANODE_2") (pintype "bidirectional"))
      (node (ref "MCP73831") (pin "4") (pinfunction "VIN_4") (pintype "power_in"))
      (node (ref "PFMF.050.1") (pin "2") (pinfunction "2_2") (pintype "passive"))
      (node (ref "Q1") (pin "1") (pinfunction "G_1") (pintype "bidirectional"))
      (node (ref "R1_PWRUSB") (pin "2") (pinfunction "2_2") (pintype "passive"))
      (node (ref "TP14") (pin "TP") (pinfunction "TP_TP") (pintype "input"))
    )
    (net (code "56") (name "VRTC") (class "Default")
      (node (ref "C10_SUPERCAP") (pin "2") (pinfunction "2_2") (pintype "passive"))
      (node (ref "C11") (pin "1") (pinfunction "1_1") (pintype "passive"))
      (node (ref "R_CAPACITATOR") (pin "1") (pinfunction "1_1") (pintype "passive"))
      (node (ref "U3") (pin "14") (pinfunction "VBAT_14") (pintype "power_in"))
    )
    (net (code "57") (name "VUSB") (class "Default")
      (node (ref "J2") (pin "A4") (pinfunction "A4_A4") (pintype "bidirectional"))
      (node (ref "J2") (pin "A9") (pinfunction "A9_A9") (pintype "bidirectional"))
      (node (ref "J2") (pin "B4") (pinfunction "B4_B4") (pintype "bidirectional"))
      (node (ref "J2") (pin "B9") (pinfunction "B9_B9") (pintype "bidirectional"))
      (node (ref "PFMF.050.1") (pin "1") (pinfunction "1_1") (pintype "passive"))
    )
    (net (code "58") (name "unconnected-(IC1-NC-Pad4)") (class "Default")
      (node (ref "IC1") (pin "4") (pinfunction "NC_4") (pintype "no_connect"))
    )
    (net (code "59") (name "unconnected-(IC4-NC-Pad4)") (class "Default")
      (node (ref "IC4") (pin "4") (pinfunction "NC_4") (pintype "no_connect"))
    )
    (net (code "60") (name "unconnected-(J1-Pad1)") (class "Default")
      (node (ref "J1") (pin "1") (pinfunction "1_1") (pintype "bidirectional"))
    )
    (net (code "61") (name "unconnected-(J1-Pad6)") (class "Default")
      (node (ref "J1") (pin "6") (pinfunction "6_6") (pintype "bidirectional"))
    )
    (net (code "62") (name "unconnected-(J1-Pad7)") (class "Default")
      (node (ref "J1") (pin "7") (pinfunction "7_7") (pintype "bidirectional"))
    )
    (net (code "63") (name "unconnected-(J2-PadA8)") (class "Default")
      (node (ref "J2") (pin "A8") (pinfunction "A8_A8") (pintype "bidirectional"))
    )
    (net (code "64") (name "unconnected-(J2-PadB8)") (class "Default")
      (node (ref "J2") (pin "B8") (pinfunction "B8_B8") (pintype "bidirectional"))
    )
    (net (code "65") (name "unconnected-(J4-DAT1-PadP8)") (class "Default")
      (node (ref "J4") (pin "P8") (pinfunction "DAT1_P8") (pintype "bidirectional"))
    )
    (net (code "66") (name "unconnected-(J4-DAT2-PadP1)") (class "Default")
      (node (ref "J4") (pin "P1") (pinfunction "DAT2_P1") (pintype "bidirectional"))
    )
    (net (code "67") (name "unconnected-(J4-DETECTION_1-PadS1)") (class "Default")
      (node (ref "J4") (pin "S1") (pinfunction "DETECTION_1_S1") (pintype "bidirectional"))
    )
    (net (code "68") (name "unconnected-(J4-DETECTION_2-PadS2)") (class "Default")
      (node (ref "J4") (pin "S2") (pinfunction "DETECTION_2_S2") (pintype "bidirectional"))
    )
    (net (code "69") (name "unconnected-(U2-NC-Pad22)") (class "Default")
      (node (ref "U2") (pin "22") (pinfunction "NC_22") (pintype "no_connect"))
    )
    (net (code "70") (name "unconnected-(U4-~{ALERT}-Pad5)") (class "Default")
      (node (ref "U4") (pin "5") (pinfunction "~{ALERT}_5") (pintype "output"))
    )
  )
)
